# Jumpers_rev2.net
KiCad netlist of a schematic drawn in Altium Designer
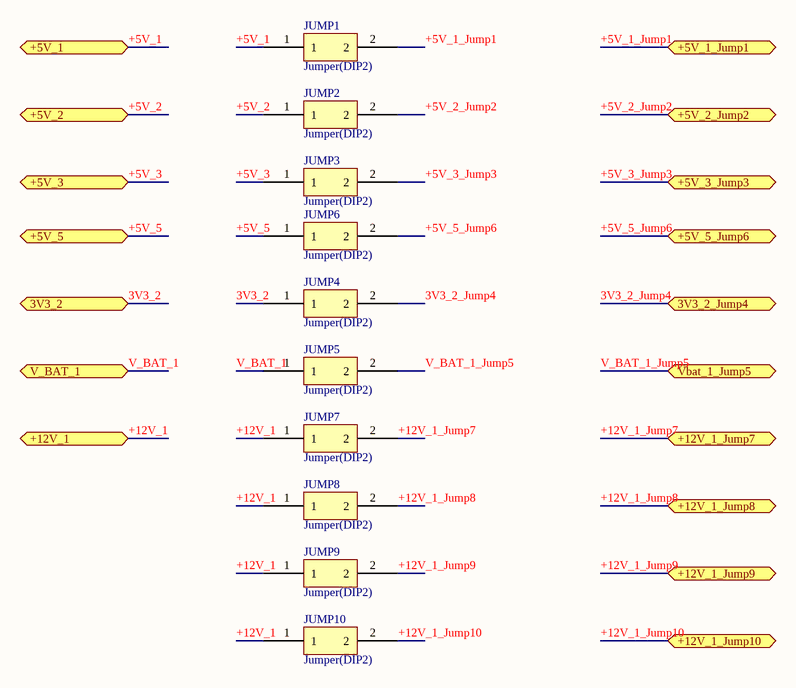
[diagram p0: Jumpers_rev2.SchDoc]

(export (version "E")
  (design (tool "Eeschema 10.0.6"))
  (components
    (comp (ref "JUMP1")
      (value "Jumper(DIP2)")
      (footprint "UmbilicalConnectors:Jumper(DIP2)")
      (libsource (lib "UmbilicalBoardV2") (part "Jumper(DIP2)"))
    )
    (comp (ref "JUMP2")
      (value "Jumper(DIP2)")
      (footprint "UmbilicalConnectors:Jumper(DIP2)")
      (libsource (lib "UmbilicalBoardV2") (part "Jumper(DIP2)"))
    )
    (comp (ref "JUMP3")
      (value "Jumper(DIP2)")
      (footprint "UmbilicalConnectors:Jumper(DIP2)")
      (libsource (lib "UmbilicalBoardV2") (part "Jumper(DIP2)"))
    )
    (comp (ref "JUMP4")
      (value "Jumper(DIP2)")
      (footprint "UmbilicalConnectors:Jumper(DIP2)")
      (libsource (lib "UmbilicalBoardV2") (part "Jumper(DIP2)"))
    )
    (comp (ref "JUMP5")
      (value "Jumper(DIP2)")
      (footprint "UmbilicalConnectors:Jumper(DIP2)")
      (libsource (lib "UmbilicalBoardV2") (part "Jumper(DIP2)"))
    )
    (comp (ref "JUMP6")
      (value "Jumper(DIP2)")
      (footprint "UmbilicalConnectors:Jumper(DIP2)")
      (libsource (lib "UmbilicalBoardV2") (part "Jumper(DIP2)"))
    )
    (comp (ref "JUMP7")
      (value "Jumper(DIP2)")
      (footprint "UmbilicalConnectors:Jumper(DIP2)")
      (libsource (lib "UmbilicalBoardV2") (part "Jumper(DIP2)"))
    )
    (comp (ref "JUMP8")
      (value "Jumper(DIP2)")
      (footprint "UmbilicalConnectors:Jumper(DIP2)")
      (libsource (lib "UmbilicalBoardV2") (part "Jumper(DIP2)"))
    )
    (comp (ref "JUMP9")
      (value "Jumper(DIP2)")
      (footprint "UmbilicalConnectors:Jumper(DIP2)")
      (libsource (lib "UmbilicalBoardV2") (part "Jumper(DIP2)"))
    )
    (comp (ref "JUMP10")
      (value "Jumper(DIP2)")
      (footprint "UmbilicalConnectors:Jumper(DIP2)")
      (libsource (lib "UmbilicalBoardV2") (part "Jumper(DIP2)"))
    )
  )
  (nets
    (net (code "1") (name "/+5V_1") (class "Default")
      (node (ref "JUMP1") (pin "1") (pinfunction "1_1") (pintype "passive"))
    )
    (net (code "2") (name "/+5V_1_Jump1") (class "Default")
      (node (ref "JUMP1") (pin "2") (pinfunction "2_2") (pintype "passive"))
    )
    (net (code "3") (name "/+5V_2") (class "Default")
      (node (ref "JUMP2") (pin "1") (pinfunction "1_1") (pintype "passive"))
    )
    (net (code "4") (name "/+5V_2_Jump2") (class "Default")
      (node (ref "JUMP2") (pin "2") (pinfunction "2_2") (pintype "passive"))
    )
    (net (code "5") (name "/+5V_3") (class "Default")
      (node (ref "JUMP3") (pin "1") (pinfunction "1_1") (pintype "passive"))
    )
    (net (code "6") (name "/+5V_3_Jump3") (class "Default")
      (node (ref "JUMP3") (pin "2") (pinfunction "2_2") (pintype "passive"))
    )
    (net (code "7") (name "/+5V_5") (class "Default")
      (node (ref "JUMP6") (pin "1") (pinfunction "1_1") (pintype "passive"))
    )
    (net (code "8") (name "/+5V_5_Jump6") (class "Default")
      (node (ref "JUMP6") (pin "2") (pinfunction "2_2") (pintype "passive"))
    )
    (net (code "9") (name "/+12V_1") (class "Default")
      (node (ref "JUMP10") (pin "1") (pinfunction "1_1") (pintype "passive"))
      (node (ref "JUMP7") (pin "1") (pinfunction "1_1") (pintype "passive"))
      (node (ref "JUMP8") (pin "1") (pinfunction "1_1") (pintype "passive"))
      (node (ref "JUMP9") (pin "1") (pinfunction "1_1") (pintype "passive"))
    )
    (net (code "10") (name "/+12V_1_Jump7") (class "Default")
      (node (ref "JUMP7") (pin "2") (pinfunction "2_2") (pintype "passive"))
    )
    (net (code "11") (name "/+12V_1_Jump8") (class "Default")
      (node (ref "JUMP8") (pin "2") (pinfunction "2_2") (pintype "passive"))
    )
    (net (code "12") (name "/+12V_1_Jump9") (class "Default")
      (node (ref "JUMP9") (pin "2") (pinfunction "2_2") (pintype "passive"))
    )
    (net (code "13") (name "/+12V_1_Jump10") (class "Default")
      (node (ref "JUMP10") (pin "2") (pinfunction "2_2") (pintype "passive"))
    )
    (net (code "14") (name "/3V3_2") (class "Default")
      (node (ref "JUMP4") (pin "1") (pinfunction "1_1") (pintype "passive"))
    )
    (net (code "15") (name "/3V3_2_Jump4") (class "Default")
      (node (ref "JUMP4") (pin "2") (pinfunction "2_2") (pintype "passive"))
    )
    (net (code "16") (name "/V_BAT_1") (class "Default")
      (node (ref "JUMP5") (pin "1") (pinfunction "1_1") (pintype "passive"))
    )
    (net (code "17") (name "/V_BAT_1_Jump5") (class "Default")
      (node (ref "JUMP5") (pin "2") (pinfunction "2_2") (pintype "passive"))
    )
  )
)
